# SAD_1_1.net
KiCad netlist of a schematic drawn in EAGLE
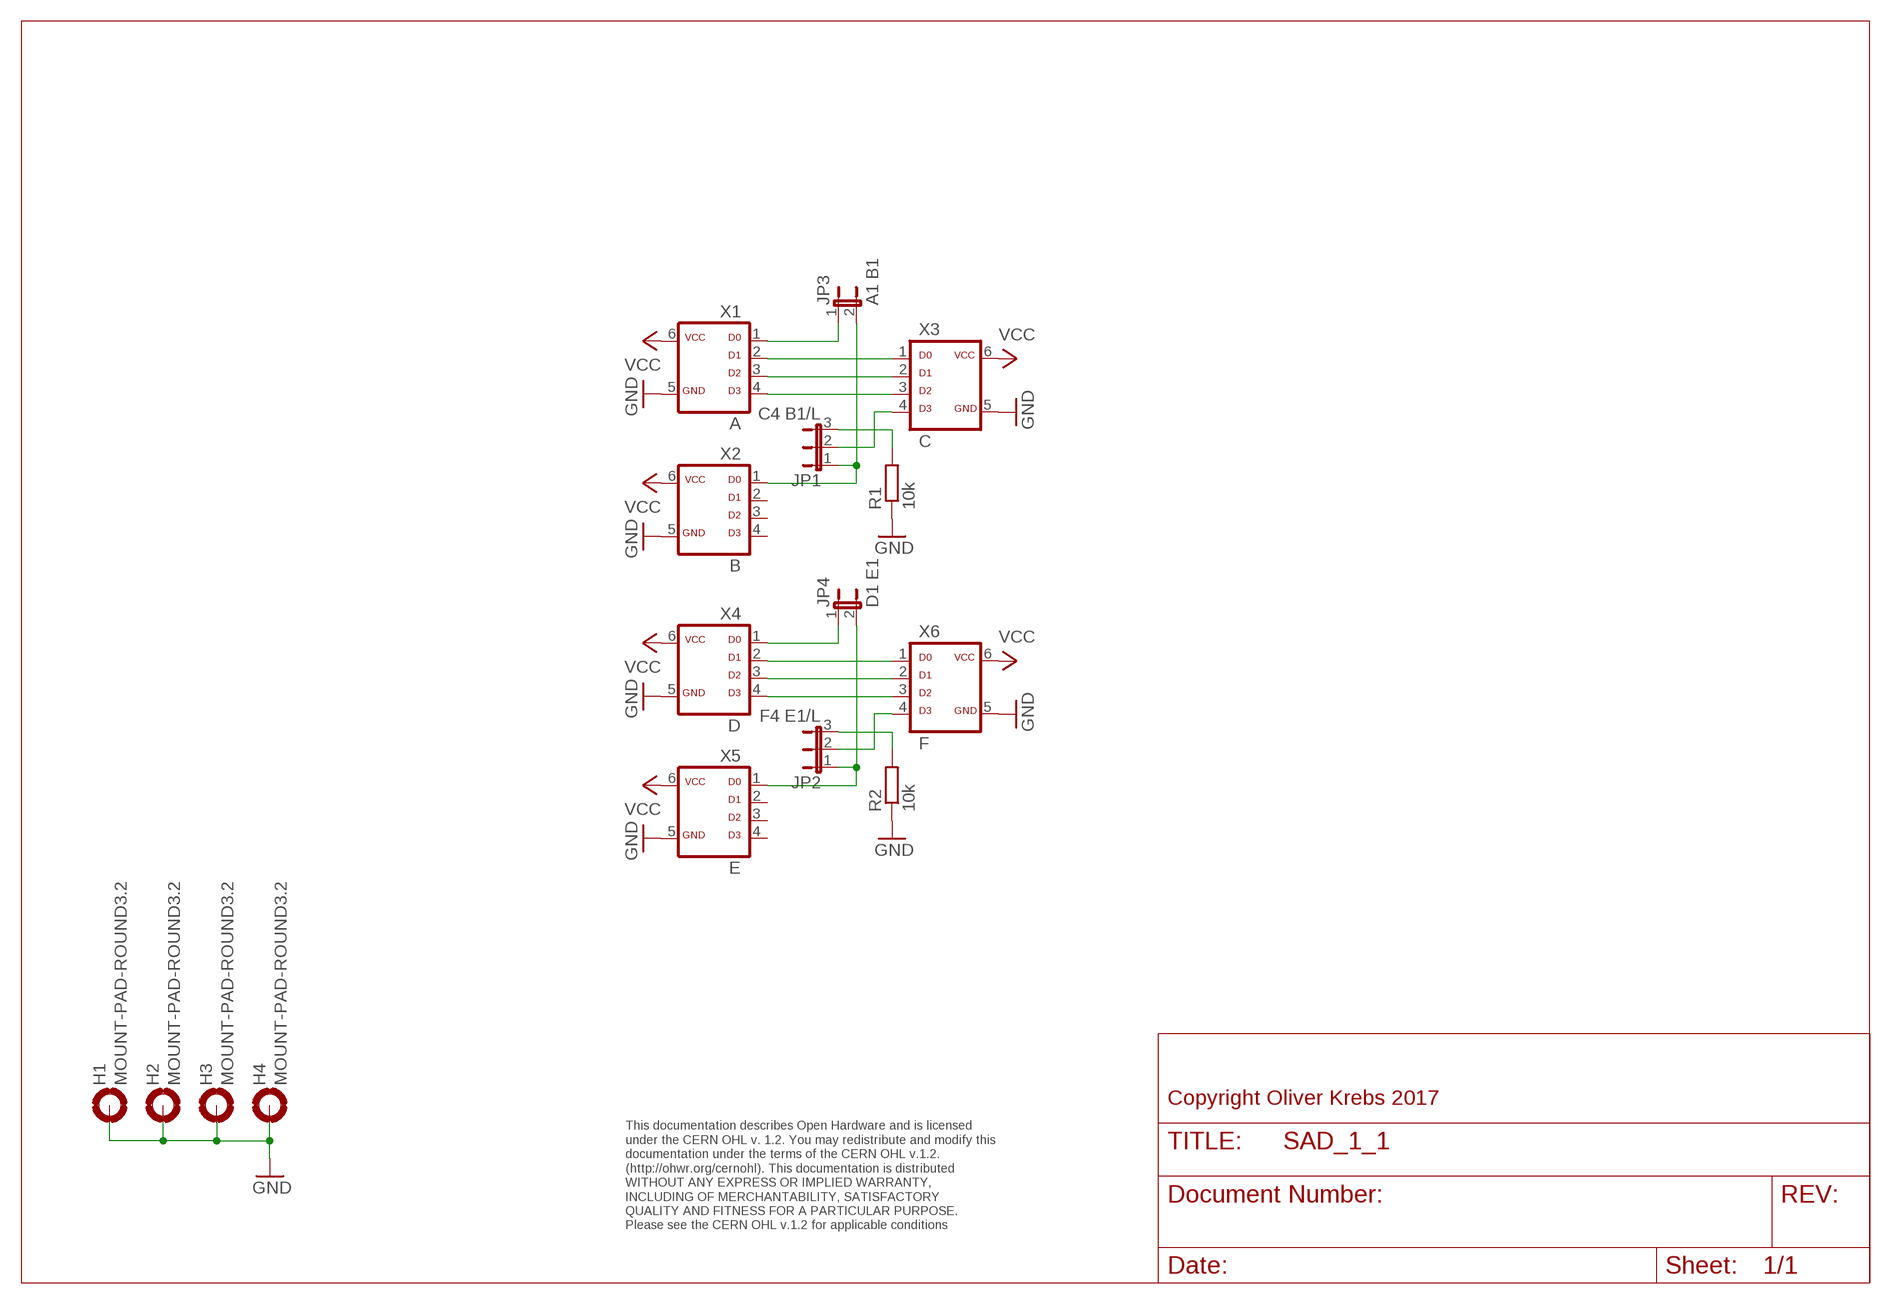
[diagram p0: schematic, sheet 1]

(export (version "E")
  (design (tool "Eeschema 10.0.6"))
  (components
    (comp (ref "H1")
      (value "MOUNT-PAD-ROUND3.2")
      (footprint "eagle-import:3,2-PAD")
      (libsource (lib "eagle-import") (part "MOUNT-PAD-ROUND3.2"))
    )
    (comp (ref "H2")
      (value "MOUNT-PAD-ROUND3.2")
      (footprint "eagle-import:3,2-PAD")
      (libsource (lib "eagle-import") (part "MOUNT-PAD-ROUND3.2"))
    )
    (comp (ref "H3")
      (value "MOUNT-PAD-ROUND3.2")
      (footprint "eagle-import:3,2-PAD")
      (libsource (lib "eagle-import") (part "MOUNT-PAD-ROUND3.2"))
    )
    (comp (ref "H4")
      (value "MOUNT-PAD-ROUND3.2")
      (footprint "eagle-import:3,2-PAD")
      (libsource (lib "eagle-import") (part "MOUNT-PAD-ROUND3.2"))
    )
    (comp (ref "JP1")
      (value "C4 B1/L")
      (footprint "eagle-import:JP2")
      (libsource (lib "eagle-import") (part "JP2E"))
    )
    (comp (ref "JP2")
      (value "F4 E1/L")
      (footprint "eagle-import:JP2")
      (libsource (lib "eagle-import") (part "JP2E"))
    )
    (comp (ref "JP3")
      (value "A1 B1")
      (footprint "eagle-import:JP1")
      (libsource (lib "eagle-import") (part "JP1E"))
    )
    (comp (ref "JP4")
      (value "D1 E1")
      (footprint "eagle-import:JP1")
      (libsource (lib "eagle-import") (part "JP1E"))
    )
    (comp (ref "R1")
      (value "10k")
      (footprint "eagle-import:0207_10")
      (libsource (lib "eagle-import") (part "R-EU_0207/10"))
    )
    (comp (ref "R2")
      (value "10k")
      (footprint "eagle-import:0207_10")
      (libsource (lib "eagle-import") (part "R-EU_0207/10"))
    )
    (comp (ref "X1")
      (value "A")
      (footprint "eagle-import:ML-6")
      (libsource (lib "eagle-import") (part "ML6D"))
    )
    (comp (ref "X2")
      (value "B")
      (footprint "eagle-import:ML-6")
      (libsource (lib "eagle-import") (part "ML6D"))
    )
    (comp (ref "X3")
      (value "C")
      (footprint "eagle-import:ML-6")
      (libsource (lib "eagle-import") (part "ML6D"))
    )
    (comp (ref "X4")
      (value "D")
      (footprint "eagle-import:ML-6")
      (libsource (lib "eagle-import") (part "ML6D"))
    )
    (comp (ref "X5")
      (value "E")
      (footprint "eagle-import:ML-6")
      (libsource (lib "eagle-import") (part "ML6D"))
    )
    (comp (ref "X6")
      (value "F")
      (footprint "eagle-import:ML-6")
      (libsource (lib "eagle-import") (part "ML6D"))
    )
  )
  (nets
    (net (code "1") (name "GND") (class "Default")
      (node (ref "H1") (pin "B3,2") (pinfunction "MOUNT_B3,2") (pintype "passive"))
      (node (ref "H2") (pin "B3,2") (pinfunction "MOUNT_B3,2") (pintype "passive"))
      (node (ref "H3") (pin "B3,2") (pinfunction "MOUNT_B3,2") (pintype "passive"))
      (node (ref "H4") (pin "B3,2") (pinfunction "MOUNT_B3,2") (pintype "passive"))
      (node (ref "R1") (pin "1") (pinfunction "1_1") (pintype "passive"))
      (node (ref "R2") (pin "1") (pinfunction "1_1") (pintype "passive"))
      (node (ref "X1") (pin "5") (pinfunction "5_5") (pintype "passive"))
      (node (ref "X2") (pin "5") (pinfunction "5_5") (pintype "passive"))
      (node (ref "X3") (pin "5") (pinfunction "5_5") (pintype "passive"))
      (node (ref "X4") (pin "5") (pinfunction "5_5") (pintype "passive"))
      (node (ref "X5") (pin "5") (pinfunction "5_5") (pintype "passive"))
      (node (ref "X6") (pin "5") (pinfunction "5_5") (pintype "passive"))
    )
    (net (code "2") (name "Net-(JP1-Pad1)") (class "Default")
      (node (ref "JP1") (pin "1") (pinfunction "1_1") (pintype "passive"))
      (node (ref "JP3") (pin "2") (pinfunction "2_2") (pintype "passive"))
      (node (ref "X2") (pin "1") (pinfunction "1_1") (pintype "passive"))
    )
    (net (code "3") (name "Net-(JP1-Pad2)") (class "Default")
      (node (ref "JP1") (pin "2") (pinfunction "2_2") (pintype "passive"))
      (node (ref "X3") (pin "4") (pinfunction "4_4") (pintype "passive"))
    )
    (net (code "4") (name "Net-(JP1-Pad3)") (class "Default")
      (node (ref "JP1") (pin "3") (pinfunction "3_3") (pintype "passive"))
      (node (ref "R1") (pin "2") (pinfunction "2_2") (pintype "passive"))
    )
    (net (code "5") (name "Net-(JP2-Pad1)") (class "Default")
      (node (ref "JP2") (pin "1") (pinfunction "1_1") (pintype "passive"))
      (node (ref "JP4") (pin "2") (pinfunction "2_2") (pintype "passive"))
      (node (ref "X5") (pin "1") (pinfunction "1_1") (pintype "passive"))
    )
    (net (code "6") (name "Net-(JP2-Pad2)") (class "Default")
      (node (ref "JP2") (pin "2") (pinfunction "2_2") (pintype "passive"))
      (node (ref "X6") (pin "4") (pinfunction "4_4") (pintype "passive"))
    )
    (net (code "7") (name "Net-(JP2-Pad3)") (class "Default")
      (node (ref "JP2") (pin "3") (pinfunction "3_3") (pintype "passive"))
      (node (ref "R2") (pin "2") (pinfunction "2_2") (pintype "passive"))
    )
    (net (code "8") (name "Net-(JP3-Pad1)") (class "Default")
      (node (ref "JP3") (pin "1") (pinfunction "1_1") (pintype "passive"))
      (node (ref "X1") (pin "1") (pinfunction "1_1") (pintype "passive"))
    )
    (net (code "9") (name "Net-(JP4-Pad1)") (class "Default")
      (node (ref "JP4") (pin "1") (pinfunction "1_1") (pintype "passive"))
      (node (ref "X4") (pin "1") (pinfunction "1_1") (pintype "passive"))
    )
    (net (code "10") (name "Net-(X1-Pad2)") (class "Default")
      (node (ref "X1") (pin "2") (pinfunction "2_2") (pintype "passive"))
      (node (ref "X3") (pin "1") (pinfunction "1_1") (pintype "passive"))
    )
    (net (code "11") (name "Net-(X1-Pad3)") (class "Default")
      (node (ref "X1") (pin "3") (pinfunction "3_3") (pintype "passive"))
      (node (ref "X3") (pin "2") (pinfunction "2_2") (pintype "passive"))
    )
    (net (code "12") (name "Net-(X1-Pad4)") (class "Default")
      (node (ref "X1") (pin "4") (pinfunction "4_4") (pintype "passive"))
      (node (ref "X3") (pin "3") (pinfunction "3_3") (pintype "passive"))
    )
    (net (code "13") (name "Net-(X4-Pad2)") (class "Default")
      (node (ref "X4") (pin "2") (pinfunction "2_2") (pintype "passive"))
      (node (ref "X6") (pin "1") (pinfunction "1_1") (pintype "passive"))
    )
    (net (code "14") (name "Net-(X4-Pad3)") (class "Default")
      (node (ref "X4") (pin "3") (pinfunction "3_3") (pintype "passive"))
      (node (ref "X6") (pin "2") (pinfunction "2_2") (pintype "passive"))
    )
    (net (code "15") (name "Net-(X4-Pad4)") (class "Default")
      (node (ref "X4") (pin "4") (pinfunction "4_4") (pintype "passive"))
      (node (ref "X6") (pin "3") (pinfunction "3_3") (pintype "passive"))
    )
    (net (code "16") (name "VCC") (class "Default")
      (node (ref "X1") (pin "6") (pinfunction "6_6") (pintype "passive"))
      (node (ref "X2") (pin "6") (pinfunction "6_6") (pintype "passive"))
      (node (ref "X3") (pin "6") (pinfunction "6_6") (pintype "passive"))
      (node (ref "X4") (pin "6") (pinfunction "6_6") (pintype "passive"))
      (node (ref "X5") (pin "6") (pinfunction "6_6") (pintype "passive"))
      (node (ref "X6") (pin "6") (pinfunction "6_6") (pintype "passive"))
    )
    (net (code "17") (name "unconnected-(X2-Pad2)") (class "Default")
      (node (ref "X2") (pin "2") (pinfunction "2_2") (pintype "passive"))
    )
    (net (code "18") (name "unconnected-(X2-Pad3)") (class "Default")
      (node (ref "X2") (pin "3") (pinfunction "3_3") (pintype "passive"))
    )
    (net (code "19") (name "unconnected-(X2-Pad4)") (class "Default")
      (node (ref "X2") (pin "4") (pinfunction "4_4") (pintype "passive"))
    )
    (net (code "20") (name "unconnected-(X5-Pad2)") (class "Default")
      (node (ref "X5") (pin "2") (pinfunction "2_2") (pintype "passive"))
    )
    (net (code "21") (name "unconnected-(X5-Pad3)") (class "Default")
      (node (ref "X5") (pin "3") (pinfunction "3_3") (pintype "passive"))
    )
    (net (code "22") (name "unconnected-(X5-Pad4)") (class "Default")
      (node (ref "X5") (pin "4") (pinfunction "4_4") (pintype "passive"))
    )
  )
)
